# telecommandeB.net
KiCad netlist of a schematic drawn in EAGLE
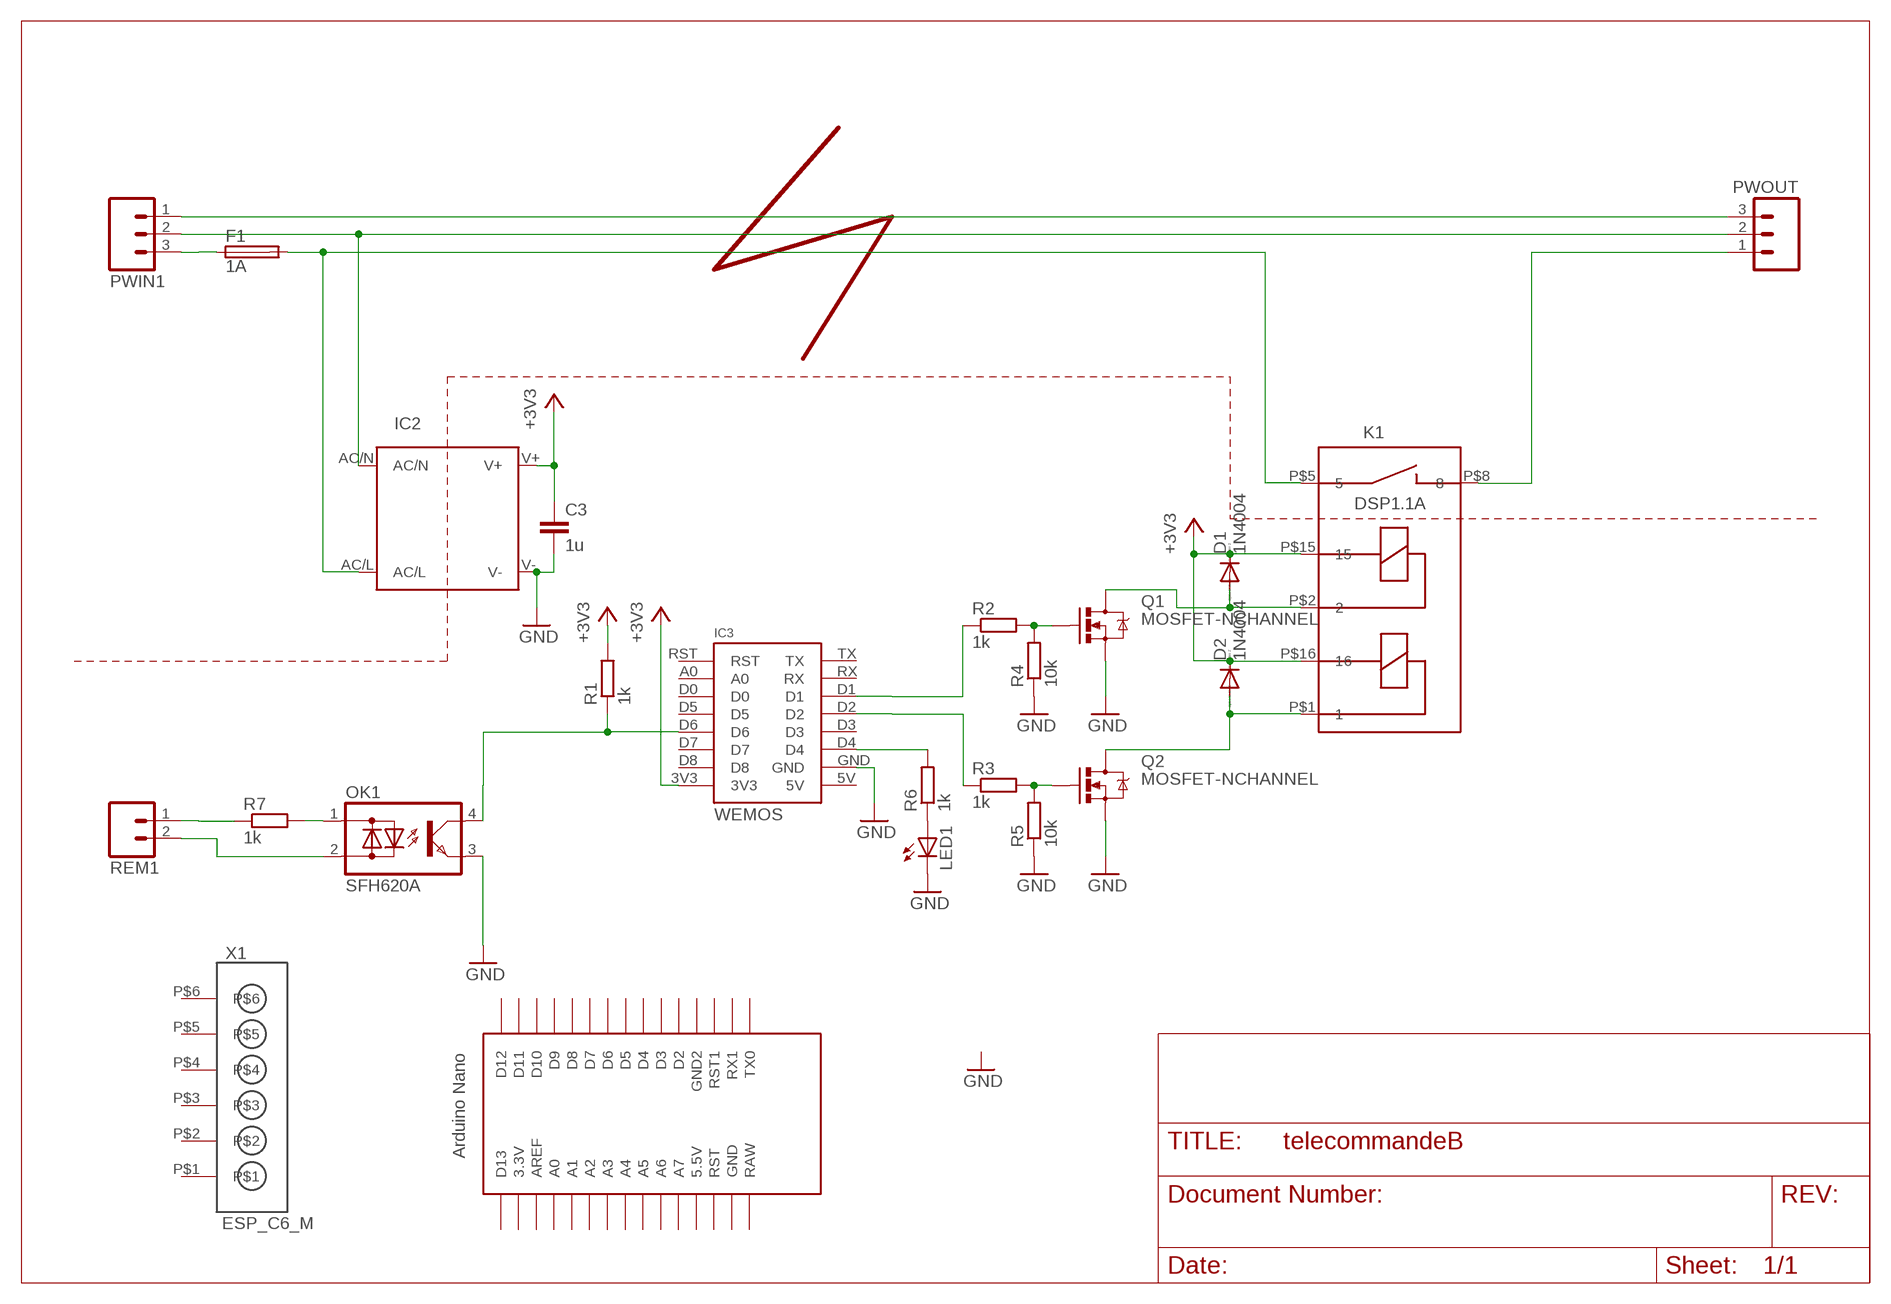
[diagram p0: schematic, sheet 1]

(export (version "E")
  (design (tool "Eeschema 10.0.6"))
  (components
    (comp (ref "C3")
      (value "1u")
      (footprint "eagle-import:C025-024X044")
      (libsource (lib "eagle-import") (part "C-EU025-024X044"))
    )
    (comp (ref "D1")
      (value "1N4004")
      (footprint "eagle-import:DO41-10")
      (libsource (lib "eagle-import") (part "1N4004"))
    )
    (comp (ref "D2")
      (value "1N4004")
      (footprint "eagle-import:DO41-10")
      (libsource (lib "eagle-import") (part "1N4004"))
    )
    (comp (ref "F1")
      (value "1A")
      (footprint "eagle-import:GSH15")
      (fields (field (name "MPN") "64900001039"))
      (libsource (lib "eagle-import") (part "GSH15"))
    )
    (comp (ref "IC2")
      (value "IRM_03")
      (footprint "eagle-import:IRM_03")
      (libsource (lib "eagle-import") (part "IRM_03"))
    )
    (comp (ref "IC3")
      (value "WEMOS")
      (footprint "eagle-import:WEMOS")
      (libsource (lib "eagle-import") (part "WEMOS"))
    )
    (comp (ref "K1")
      (value "DSP1.1A")
      (footprint "eagle-import:DSP1A")
      (libsource (lib "eagle-import") (part "DSP1.1A"))
    )
    (comp (ref "LED1")
      (value "LED3MM")
      (footprint "eagle-import:LED3MM")
      (libsource (lib "eagle-import") (part "LED3MM"))
    )
    (comp (ref "OK1")
      (value "SFH620A")
      (footprint "eagle-import:DIL04")
      (fields (field (name "MPN") "SFH620A-2"))
      (libsource (lib "eagle-import") (part "SFH620A"))
    )
    (comp (ref "PWIN1")
      (value "M03-SCREW-5MM")
      (footprint "eagle-import:SCREWTERMINAL-5MM-3")
      (libsource (lib "eagle-import") (part "M03-SCREW-5MM"))
    )
    (comp (ref "PWOUT")
      (value "M03-SCREW-5MM")
      (footprint "eagle-import:SCREWTERMINAL-5MM-3")
      (libsource (lib "eagle-import") (part "M03-SCREW-5MM"))
    )
    (comp (ref "Q1")
      (value "MOSFET-NCHANNEL")
      (footprint "eagle-import:TO-92-L")
      (libsource (lib "eagle-import") (part "MOSFET-NCHANNEL"))
    )
    (comp (ref "Q2")
      (value "MOSFET-NCHANNEL")
      (footprint "eagle-import:TO-92-L")
      (libsource (lib "eagle-import") (part "MOSFET-NCHANNEL"))
    )
    (comp (ref "R1")
      (value "1k")
      (footprint "eagle-import:0207_10")
      (libsource (lib "eagle-import") (part "R-EU_0207/10"))
    )
    (comp (ref "R2")
      (value "1k")
      (footprint "eagle-import:0204_7")
      (libsource (lib "eagle-import") (part "R-EU_0204/7"))
    )
    (comp (ref "R3")
      (value "1k")
      (footprint "eagle-import:0204_7")
      (libsource (lib "eagle-import") (part "R-EU_0204/7"))
    )
    (comp (ref "R4")
      (value "10k")
      (footprint "eagle-import:0204_7")
      (libsource (lib "eagle-import") (part "R-EU_0204/7"))
    )
    (comp (ref "R5")
      (value "10k")
      (footprint "eagle-import:0204_7")
      (libsource (lib "eagle-import") (part "R-EU_0204/7"))
    )
    (comp (ref "R6")
      (value "1k")
      (footprint "eagle-import:0204_7")
      (libsource (lib "eagle-import") (part "R-EU_0204/7"))
    )
    (comp (ref "R7")
      (value "1k")
      (footprint "eagle-import:0207_10")
      (libsource (lib "eagle-import") (part "R-EU_0207/10"))
    )
    (comp (ref "REM1")
      (value "M025MM")
      (footprint "eagle-import:SCREWTERMINAL-5MM-2")
      (libsource (lib "eagle-import") (part "M025MM"))
    )
    (comp (ref "U$1")
      (value "NANO")
      (footprint "eagle-import:NANO")
      (libsource (lib "eagle-import") (part "NANO"))
    )
    (comp (ref "X1")
      (value "ESP_C6_M")
      (footprint "eagle-import:ESP-CONNECT-6")
      (libsource (lib "eagle-import") (part "ESP_C6_M"))
    )
  )
  (nets
    (net (code "1") (name "+3V3") (class "Default")
      (node (ref "C3") (pin "1") (pinfunction "1_1") (pintype "passive"))
      (node (ref "D1") (pin "C") (pinfunction "C_C") (pintype "passive"))
      (node (ref "D2") (pin "C") (pinfunction "C_C") (pintype "passive"))
      (node (ref "IC2") (pin "V+") (pinfunction "V+_V+") (pintype "output"))
      (node (ref "IC3") (pin "3V3") (pinfunction "3V3_3V3") (pintype "bidirectional"))
      (node (ref "K1") (pin "P$15") (pinfunction "15_P$15") (pintype "bidirectional"))
      (node (ref "K1") (pin "P$16") (pinfunction "16_P$16") (pintype "bidirectional"))
      (node (ref "R1") (pin "2") (pinfunction "2_2") (pintype "passive"))
    )
    (net (code "2") (name "GND") (class "Default")
      (node (ref "C3") (pin "2") (pinfunction "2_2") (pintype "passive"))
      (node (ref "IC2") (pin "V-") (pinfunction "V-_V-") (pintype "output"))
      (node (ref "IC3") (pin "GND") (pinfunction "GND_GND") (pintype "bidirectional"))
      (node (ref "LED1") (pin "K") (pinfunction "C_K") (pintype "passive"))
      (node (ref "OK1") (pin "3") (pinfunction "E_3") (pintype "passive"))
      (node (ref "Q1") (pin "P$1") (pinfunction "S_P$1") (pintype "passive"))
      (node (ref "Q2") (pin "P$1") (pinfunction "S_P$1") (pintype "passive"))
      (node (ref "R4") (pin "1") (pinfunction "1_1") (pintype "passive"))
      (node (ref "R5") (pin "1") (pinfunction "1_1") (pintype "passive"))
    )
    (net (code "3") (name "Net-(F1-Pad1)") (class "Default")
      (node (ref "F1") (pin "1") (pinfunction "1_1") (pintype "passive"))
      (node (ref "PWIN1") (pin "3") (pinfunction "3_3") (pintype "passive"))
    )
    (net (code "4") (name "Net-(IC2-PadAC{slash}N)") (class "Default")
      (node (ref "IC2") (pin "AC/N") (pinfunction "AC/N_AC/N") (pintype "input"))
      (node (ref "PWIN1") (pin "2") (pinfunction "2_2") (pintype "passive"))
      (node (ref "PWOUT") (pin "2") (pinfunction "2_2") (pintype "passive"))
    )
    (net (code "5") (name "Net-(IC3-PadD1)") (class "Default")
      (node (ref "IC3") (pin "D1") (pinfunction "D1_D1") (pintype "bidirectional"))
      (node (ref "R2") (pin "1") (pinfunction "1_1") (pintype "passive"))
    )
    (net (code "6") (name "Net-(IC3-PadD2)") (class "Default")
      (node (ref "IC3") (pin "D2") (pinfunction "D2_D2") (pintype "bidirectional"))
      (node (ref "R3") (pin "1") (pinfunction "1_1") (pintype "passive"))
    )
    (net (code "7") (name "Net-(IC3-PadD4)") (class "Default")
      (node (ref "IC3") (pin "D4") (pinfunction "D4_D4") (pintype "bidirectional"))
      (node (ref "R6") (pin "2") (pinfunction "2_2") (pintype "passive"))
    )
    (net (code "8") (name "Net-(K1-1)") (class "Default")
      (node (ref "D2") (pin "A") (pinfunction "A_A") (pintype "passive"))
      (node (ref "K1") (pin "P$1") (pinfunction "1_P$1") (pintype "bidirectional"))
      (node (ref "Q2") (pin "P$3") (pinfunction "D_P$3") (pintype "passive"))
    )
    (net (code "9") (name "Net-(K1-2)") (class "Default")
      (node (ref "D1") (pin "A") (pinfunction "A_A") (pintype "passive"))
      (node (ref "K1") (pin "P$2") (pinfunction "2_P$2") (pintype "bidirectional"))
      (node (ref "Q1") (pin "P$3") (pinfunction "D_P$3") (pintype "passive"))
    )
    (net (code "10") (name "Net-(K1-5)") (class "Default")
      (node (ref "F1") (pin "2") (pinfunction "2_2") (pintype "passive"))
      (node (ref "IC2") (pin "AC/L") (pinfunction "AC/L_AC/L") (pintype "input"))
      (node (ref "K1") (pin "P$5") (pinfunction "5_P$5") (pintype "bidirectional"))
    )
    (net (code "11") (name "Net-(K1-8)") (class "Default")
      (node (ref "K1") (pin "P$8") (pinfunction "8_P$8") (pintype "bidirectional"))
      (node (ref "PWOUT") (pin "1") (pinfunction "1_1") (pintype "passive"))
    )
    (net (code "12") (name "Net-(LED1-PadA)") (class "Default")
      (node (ref "LED1") (pin "A") (pinfunction "A_A") (pintype "passive"))
      (node (ref "R6") (pin "1") (pinfunction "1_1") (pintype "passive"))
    )
    (net (code "13") (name "Net-(OK1-AC1)") (class "Default")
      (node (ref "OK1") (pin "1") (pinfunction "AC1_1") (pintype "passive"))
      (node (ref "R7") (pin "2") (pinfunction "2_2") (pintype "passive"))
    )
    (net (code "14") (name "Net-(OK1-AC2)") (class "Default")
      (node (ref "OK1") (pin "2") (pinfunction "AC2_2") (pintype "passive"))
      (node (ref "REM1") (pin "2") (pinfunction "2_2") (pintype "passive"))
    )
    (net (code "15") (name "Net-(OK1-C)") (class "Default")
      (node (ref "IC3") (pin "D6") (pinfunction "D6_D6") (pintype "bidirectional"))
      (node (ref "OK1") (pin "4") (pinfunction "C_4") (pintype "passive"))
      (node (ref "R1") (pin "1") (pinfunction "1_1") (pintype "passive"))
    )
    (net (code "16") (name "Net-(PWIN1-Pad1)") (class "Default")
      (node (ref "PWIN1") (pin "1") (pinfunction "1_1") (pintype "passive"))
      (node (ref "PWOUT") (pin "3") (pinfunction "3_3") (pintype "passive"))
    )
    (net (code "17") (name "Net-(Q1-G)") (class "Default")
      (node (ref "Q1") (pin "P$2") (pinfunction "G_P$2") (pintype "passive"))
      (node (ref "R2") (pin "2") (pinfunction "2_2") (pintype "passive"))
      (node (ref "R4") (pin "2") (pinfunction "2_2") (pintype "passive"))
    )
    (net (code "18") (name "Net-(Q2-G)") (class "Default")
      (node (ref "Q2") (pin "P$2") (pinfunction "G_P$2") (pintype "passive"))
      (node (ref "R3") (pin "2") (pinfunction "2_2") (pintype "passive"))
      (node (ref "R5") (pin "2") (pinfunction "2_2") (pintype "passive"))
    )
    (net (code "19") (name "Net-(R7-Pad1)") (class "Default")
      (node (ref "R7") (pin "1") (pinfunction "1_1") (pintype "passive"))
      (node (ref "REM1") (pin "1") (pinfunction "1_1") (pintype "passive"))
    )
    (net (code "20") (name "unconnected-(IC3-Pad5V)") (class "Default")
      (node (ref "IC3") (pin "5V") (pinfunction "5V_5V") (pintype "bidirectional"))
    )
    (net (code "21") (name "unconnected-(IC3-PadA0)") (class "Default")
      (node (ref "IC3") (pin "A0") (pinfunction "A0_A0") (pintype "bidirectional"))
    )
    (net (code "22") (name "unconnected-(IC3-PadD0)") (class "Default")
      (node (ref "IC3") (pin "D0") (pinfunction "D0_D0") (pintype "bidirectional"))
    )
    (net (code "23") (name "unconnected-(IC3-PadD3)") (class "Default")
      (node (ref "IC3") (pin "D3") (pinfunction "D3_D3") (pintype "bidirectional"))
    )
    (net (code "24") (name "unconnected-(IC3-PadD5)") (class "Default")
      (node (ref "IC3") (pin "D5") (pinfunction "D5_D5") (pintype "bidirectional"))
    )
    (net (code "25") (name "unconnected-(IC3-PadD7)") (class "Default")
      (node (ref "IC3") (pin "D7") (pinfunction "D7_D7") (pintype "bidirectional"))
    )
    (net (code "26") (name "unconnected-(IC3-PadD8)") (class "Default")
      (node (ref "IC3") (pin "D8") (pinfunction "D8_D8") (pintype "bidirectional"))
    )
    (net (code "27") (name "unconnected-(IC3-PadRST)") (class "Default")
      (node (ref "IC3") (pin "RST") (pinfunction "RST_RST") (pintype "bidirectional"))
    )
    (net (code "28") (name "unconnected-(IC3-PadRX)") (class "Default")
      (node (ref "IC3") (pin "RX") (pinfunction "RX_RX") (pintype "bidirectional"))
    )
    (net (code "29") (name "unconnected-(IC3-PadTX)") (class "Default")
      (node (ref "IC3") (pin "TX") (pinfunction "TX_TX") (pintype "bidirectional"))
    )
    (net (code "30") (name "unconnected-(U$1-5.5V-Pad5V)") (class "Default")
      (node (ref "U$1") (pin "5V") (pinfunction "5.5V_5V") (pintype "bidirectional"))
    )
    (net (code "31") (name "unconnected-(U$1-GND2-PadGND1)") (class "Default")
      (node (ref "U$1") (pin "GND1") (pinfunction "GND2_GND1") (pintype "bidirectional"))
    )
    (net (code "32") (name "unconnected-(U$1-Pad3.3V)") (class "Default")
      (node (ref "U$1") (pin "3.3V") (pinfunction "3.3V_3.3V") (pintype "bidirectional"))
    )
    (net (code "33") (name "unconnected-(U$1-PadA0)") (class "Default")
      (node (ref "U$1") (pin "A0") (pinfunction "A0_A0") (pintype "bidirectional"))
    )
    (net (code "34") (name "unconnected-(U$1-PadA1)") (class "Default")
      (node (ref "U$1") (pin "A1") (pinfunction "A1_A1") (pintype "bidirectional"))
    )
    (net (code "35") (name "unconnected-(U$1-PadA2)") (class "Default")
      (node (ref "U$1") (pin "A2") (pinfunction "A2_A2") (pintype "bidirectional"))
    )
    (net (code "36") (name "unconnected-(U$1-PadA3)") (class "Default")
      (node (ref "U$1") (pin "A3") (pinfunction "A3_A3") (pintype "bidirectional"))
    )
    (net (code "37") (name "unconnected-(U$1-PadA4)") (class "Default")
      (node (ref "U$1") (pin "A4") (pinfunction "A4_A4") (pintype "bidirectional"))
    )
    (net (code "38") (name "unconnected-(U$1-PadA5)") (class "Default")
      (node (ref "U$1") (pin "A5") (pinfunction "A5_A5") (pintype "bidirectional"))
    )
    (net (code "39") (name "unconnected-(U$1-PadA6)") (class "Default")
      (node (ref "U$1") (pin "A6") (pinfunction "A6_A6") (pintype "bidirectional"))
    )
    (net (code "40") (name "unconnected-(U$1-PadA7)") (class "Default")
      (node (ref "U$1") (pin "A7") (pinfunction "A7_A7") (pintype "bidirectional"))
    )
    (net (code "41") (name "unconnected-(U$1-PadAREF)") (class "Default")
      (node (ref "U$1") (pin "AREF") (pinfunction "AREF_AREF") (pintype "bidirectional"))
    )
    (net (code "42") (name "unconnected-(U$1-PadD2)") (class "Default")
      (node (ref "U$1") (pin "D2") (pinfunction "D2_D2") (pintype "bidirectional"))
    )
    (net (code "43") (name "unconnected-(U$1-PadD3)") (class "Default")
      (node (ref "U$1") (pin "D3") (pinfunction "D3_D3") (pintype "bidirectional"))
    )
    (net (code "44") (name "unconnected-(U$1-PadD4)") (class "Default")
      (node (ref "U$1") (pin "D4") (pinfunction "D4_D4") (pintype "bidirectional"))
    )
    (net (code "45") (name "unconnected-(U$1-PadD5)") (class "Default")
      (node (ref "U$1") (pin "D5") (pinfunction "D5_D5") (pintype "bidirectional"))
    )
    (net (code "46") (name "unconnected-(U$1-PadD6)") (class "Default")
      (node (ref "U$1") (pin "D6") (pinfunction "D6_D6") (pintype "bidirectional"))
    )
    (net (code "47") (name "unconnected-(U$1-PadD7)") (class "Default")
      (node (ref "U$1") (pin "D7") (pinfunction "D7_D7") (pintype "bidirectional"))
    )
    (net (code "48") (name "unconnected-(U$1-PadD8)") (class "Default")
      (node (ref "U$1") (pin "D8") (pinfunction "D8_D8") (pintype "bidirectional"))
    )
    (net (code "49") (name "unconnected-(U$1-PadD9)") (class "Default")
      (node (ref "U$1") (pin "D9") (pinfunction "D9_D9") (pintype "bidirectional"))
    )
    (net (code "50") (name "unconnected-(U$1-PadD10)") (class "Default")
      (node (ref "U$1") (pin "D10") (pinfunction "D10_D10") (pintype "bidirectional"))
    )
    (net (code "51") (name "unconnected-(U$1-PadD11)") (class "Default")
      (node (ref "U$1") (pin "D11") (pinfunction "D11_D11") (pintype "bidirectional"))
    )
    (net (code "52") (name "unconnected-(U$1-PadD12)") (class "Default")
      (node (ref "U$1") (pin "D12") (pinfunction "D12_D12") (pintype "bidirectional"))
    )
    (net (code "53") (name "unconnected-(U$1-PadD13)") (class "Default")
      (node (ref "U$1") (pin "D13") (pinfunction "D13_D13") (pintype "bidirectional"))
    )
    (net (code "54") (name "unconnected-(U$1-PadGND)") (class "Default")
      (node (ref "U$1") (pin "GND") (pinfunction "GND_GND") (pintype "bidirectional"))
    )
    (net (code "55") (name "unconnected-(U$1-PadICSP1)") (class "Default")
      (node (ref "U$1") (pin "ICSP1") (pinfunction "ICSP1_ICSP1") (pintype "bidirectional"))
    )
    (net (code "56") (name "unconnected-(U$1-PadICSP2)") (class "Default")
      (node (ref "U$1") (pin "ICSP2") (pinfunction "ICSP2_ICSP2") (pintype "bidirectional"))
    )
    (net (code "57") (name "unconnected-(U$1-PadICSP3)") (class "Default")
      (node (ref "U$1") (pin "ICSP3") (pinfunction "ICSP3_ICSP3") (pintype "bidirectional"))
    )
    (net (code "58") (name "unconnected-(U$1-PadICSP4)") (class "Default")
      (node (ref "U$1") (pin "ICSP4") (pinfunction "ICSP4_ICSP4") (pintype "bidirectional"))
    )
    (net (code "59") (name "unconnected-(U$1-PadICSP5)") (class "Default")
      (node (ref "U$1") (pin "ICSP5") (pinfunction "ICSP5_ICSP5") (pintype "bidirectional"))
    )
    (net (code "60") (name "unconnected-(U$1-PadICSP6)") (class "Default")
      (node (ref "U$1") (pin "ICSP6") (pinfunction "ICSP6_ICSP6") (pintype "bidirectional"))
    )
    (net (code "61") (name "unconnected-(U$1-PadRAW)") (class "Default")
      (node (ref "U$1") (pin "RAW") (pinfunction "RAW_RAW") (pintype "bidirectional"))
    )
    (net (code "62") (name "unconnected-(U$1-PadRST)") (class "Default")
      (node (ref "U$1") (pin "RST") (pinfunction "RST_RST") (pintype "bidirectional"))
    )
    (net (code "63") (name "unconnected-(U$1-PadRST1)") (class "Default")
      (node (ref "U$1") (pin "RST1") (pinfunction "RST1_RST1") (pintype "bidirectional"))
    )
    (net (code "64") (name "unconnected-(U$1-PadRX1)") (class "Default")
      (node (ref "U$1") (pin "RX1") (pinfunction "RX1_RX1") (pintype "bidirectional"))
    )
    (net (code "65") (name "unconnected-(U$1-PadTX0)") (class "Default")
      (node (ref "U$1") (pin "TX0") (pinfunction "TX0_TX0") (pintype "bidirectional"))
    )
    (net (code "66") (name "unconnected-(X1-PadP$1)") (class "Default")
      (node (ref "X1") (pin "P$1") (pinfunction "P$1_P$1") (pintype "bidirectional"))
    )
    (net (code "67") (name "unconnected-(X1-PadP$2)") (class "Default")
      (node (ref "X1") (pin "P$2") (pinfunction "P$2_P$2") (pintype "bidirectional"))
    )
    (net (code "68") (name "unconnected-(X1-PadP$3)") (class "Default")
      (node (ref "X1") (pin "P$3") (pinfunction "P$3_P$3") (pintype "bidirectional"))
    )
    (net (code "69") (name "unconnected-(X1-PadP$4)") (class "Default")
      (node (ref "X1") (pin "P$4") (pinfunction "P$4_P$4") (pintype "bidirectional"))
    )
    (net (code "70") (name "unconnected-(X1-PadP$5)") (class "Default")
      (node (ref "X1") (pin "P$5") (pinfunction "P$5_P$5") (pintype "bidirectional"))
    )
    (net (code "71") (name "unconnected-(X1-PadP$6)") (class "Default")
      (node (ref "X1") (pin "P$6") (pinfunction "P$6_P$6") (pintype "bidirectional"))
    )
  )
)
